# Zaq_HAND_SOLDERING.net
KiCad netlist of a schematic drawn in EAGLE
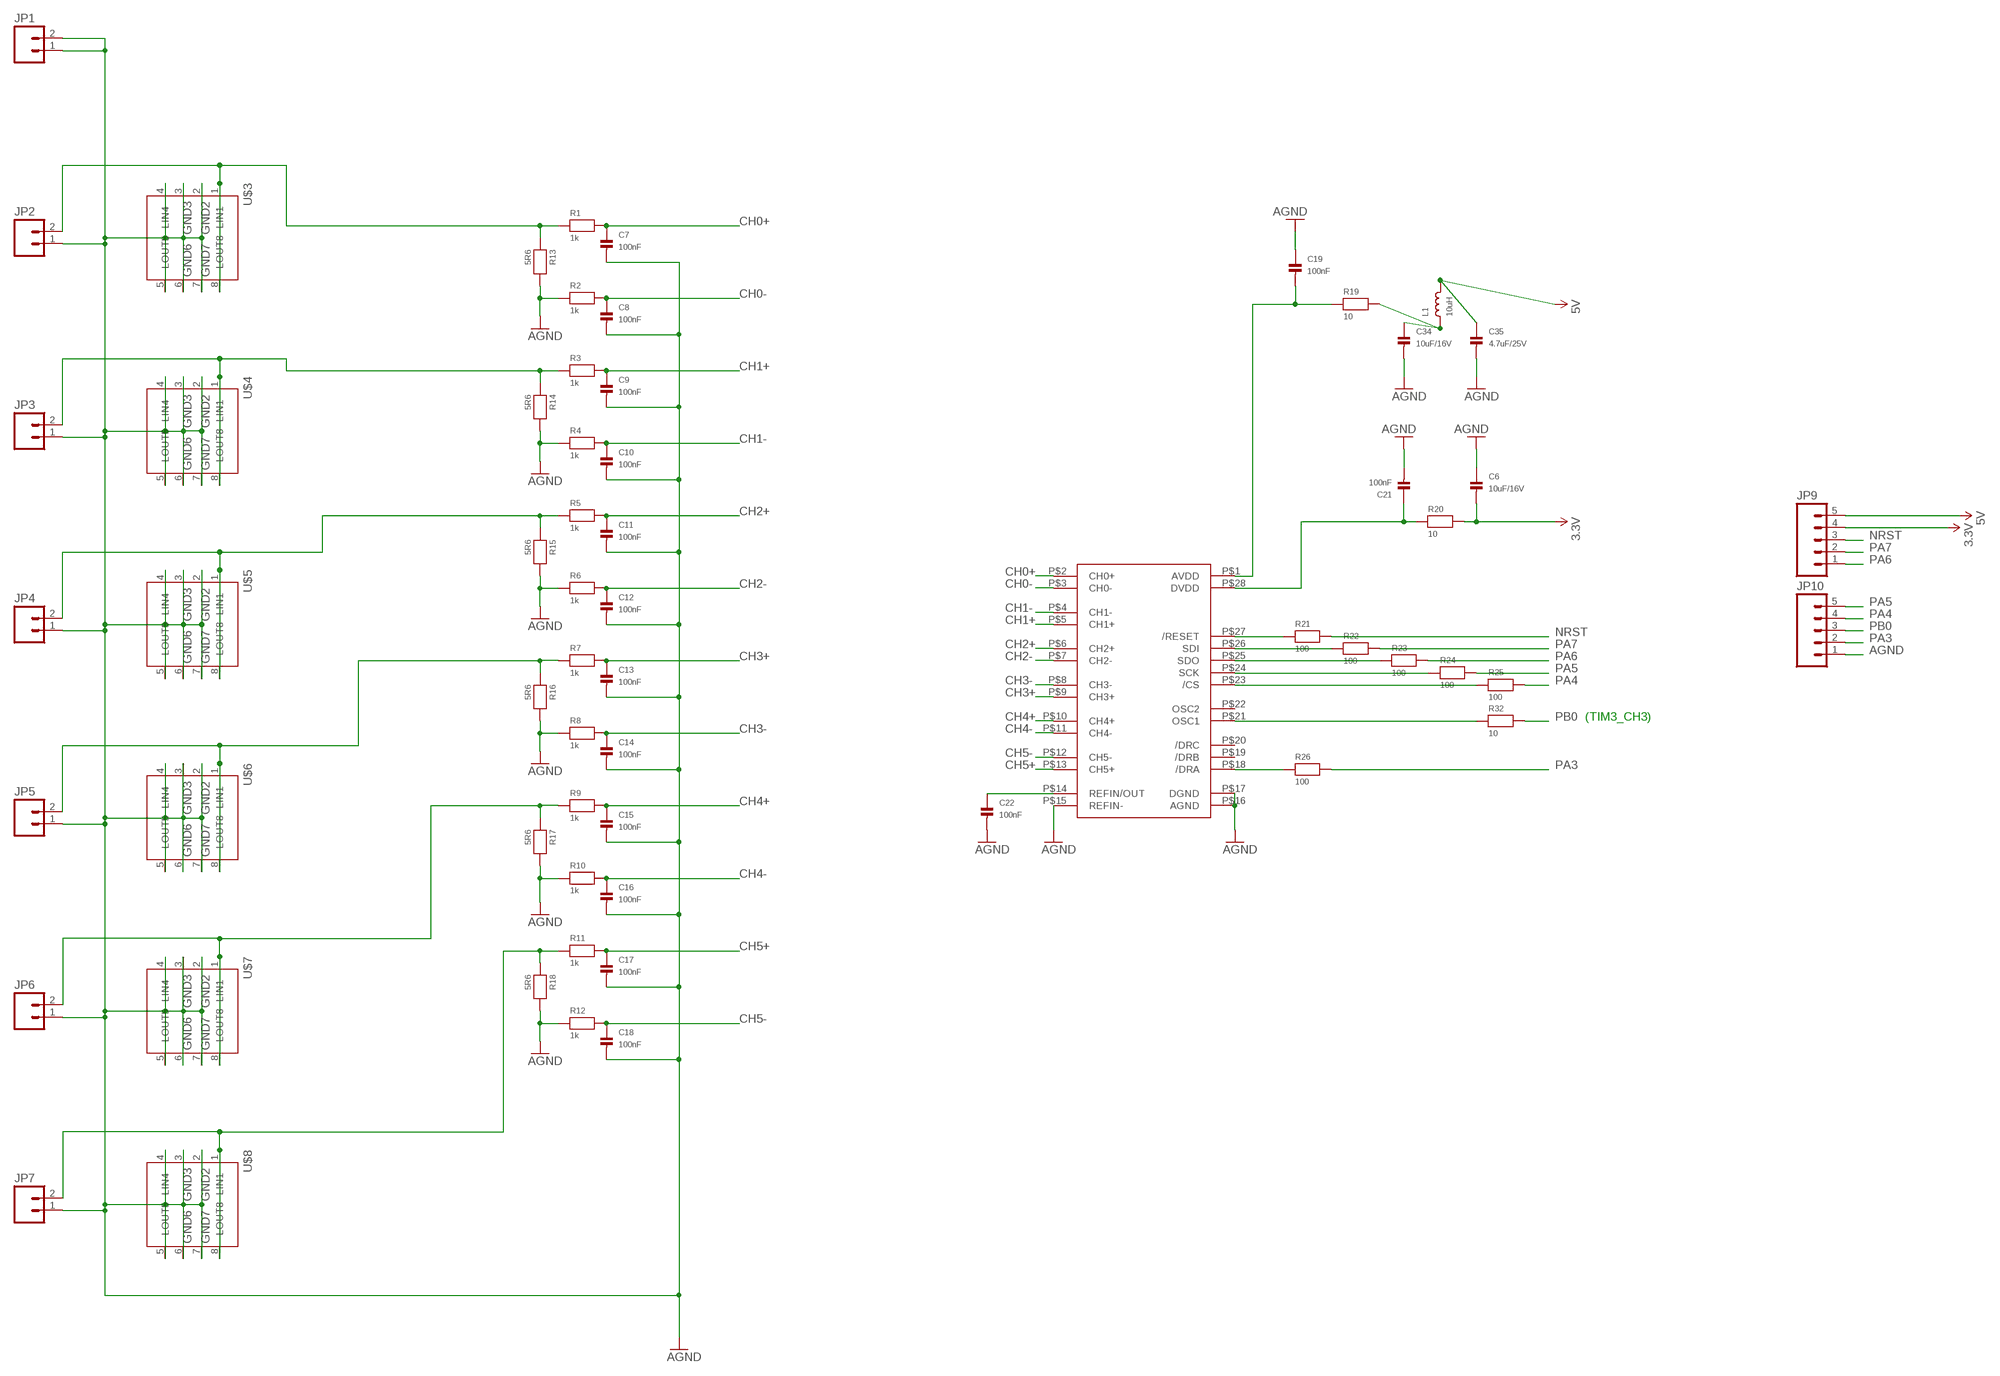
[diagram p0: schematic, sheet 1]

(export (version "E")
  (design (tool "Eeschema 10.0.6"))
  (components
    (comp (ref ".")
      (value "MCP3903")
      (footprint "eagle-import:SSOP-28")
      (libsource (lib "eagle-import") (part "MCP3903"))
    )
    (comp (ref "C6")
      (value "10uF/16V")
      (footprint "eagle-import:_0805MP")
      (libsource (lib "eagle-import") (part "CAP_CERAMIC_0805MP"))
    )
    (comp (ref "C7")
      (value "100nF")
      (footprint "eagle-import:_0805MP")
      (libsource (lib "eagle-import") (part "CAP_CERAMIC_0805MP"))
    )
    (comp (ref "C8")
      (value "100nF")
      (footprint "eagle-import:_0805MP")
      (libsource (lib "eagle-import") (part "CAP_CERAMIC_0805MP"))
    )
    (comp (ref "C9")
      (value "100nF")
      (footprint "eagle-import:_0805MP")
      (libsource (lib "eagle-import") (part "CAP_CERAMIC_0805MP"))
    )
    (comp (ref "C10")
      (value "100nF")
      (footprint "eagle-import:_0805MP")
      (libsource (lib "eagle-import") (part "CAP_CERAMIC_0805MP"))
    )
    (comp (ref "C11")
      (value "100nF")
      (footprint "eagle-import:_0805MP")
      (libsource (lib "eagle-import") (part "CAP_CERAMIC_0805MP"))
    )
    (comp (ref "C12")
      (value "100nF")
      (footprint "eagle-import:_0805MP")
      (libsource (lib "eagle-import") (part "CAP_CERAMIC_0805MP"))
    )
    (comp (ref "C13")
      (value "100nF")
      (footprint "eagle-import:_0805MP")
      (libsource (lib "eagle-import") (part "CAP_CERAMIC_0805MP"))
    )
    (comp (ref "C14")
      (value "100nF")
      (footprint "eagle-import:_0805MP")
      (libsource (lib "eagle-import") (part "CAP_CERAMIC_0805MP"))
    )
    (comp (ref "C15")
      (value "100nF")
      (footprint "eagle-import:_0805MP")
      (libsource (lib "eagle-import") (part "CAP_CERAMIC_0805MP"))
    )
    (comp (ref "C16")
      (value "100nF")
      (footprint "eagle-import:_0805MP")
      (libsource (lib "eagle-import") (part "CAP_CERAMIC_0805MP"))
    )
    (comp (ref "C17")
      (value "100nF")
      (footprint "eagle-import:_0805MP")
      (libsource (lib "eagle-import") (part "CAP_CERAMIC_0805MP"))
    )
    (comp (ref "C18")
      (value "100nF")
      (footprint "eagle-import:_0805MP")
      (libsource (lib "eagle-import") (part "CAP_CERAMIC_0805MP"))
    )
    (comp (ref "C19")
      (value "100nF")
      (footprint "eagle-import:_0805MP")
      (libsource (lib "eagle-import") (part "CAP_CERAMIC_0805MP"))
    )
    (comp (ref "C21")
      (value "100nF")
      (footprint "eagle-import:_0805MP")
      (libsource (lib "eagle-import") (part "CAP_CERAMIC_0805MP"))
    )
    (comp (ref "C22")
      (value "100nF")
      (footprint "eagle-import:_0805MP")
      (libsource (lib "eagle-import") (part "CAP_CERAMIC_0805MP"))
    )
    (comp (ref "C34")
      (value "10uF/16V")
      (footprint "eagle-import:_0805MP")
      (libsource (lib "eagle-import") (part "CAP_CERAMIC_0805MP"))
    )
    (comp (ref "C35")
      (value "4.7uF/25V")
      (footprint "eagle-import:_0805MP")
      (libsource (lib "eagle-import") (part "CAP_CERAMIC_0805MP"))
    )
    (comp (ref "JP1")
      (value "M025MM")
      (footprint "eagle-import:SCREWTERMINAL-5MM-2")
      (libsource (lib "eagle-import") (part "M025MM"))
    )
    (comp (ref "JP2")
      (value "M025MM")
      (footprint "eagle-import:SCREWTERMINAL-5MM-2")
      (libsource (lib "eagle-import") (part "M025MM"))
    )
    (comp (ref "JP3")
      (value "M025MM")
      (footprint "eagle-import:SCREWTERMINAL-5MM-2")
      (libsource (lib "eagle-import") (part "M025MM"))
    )
    (comp (ref "JP4")
      (value "M025MM")
      (footprint "eagle-import:SCREWTERMINAL-5MM-2")
      (libsource (lib "eagle-import") (part "M025MM"))
    )
    (comp (ref "JP5")
      (value "M025MM")
      (footprint "eagle-import:SCREWTERMINAL-5MM-2")
      (libsource (lib "eagle-import") (part "M025MM"))
    )
    (comp (ref "JP6")
      (value "M025MM")
      (footprint "eagle-import:SCREWTERMINAL-5MM-2")
      (libsource (lib "eagle-import") (part "M025MM"))
    )
    (comp (ref "JP7")
      (value "M025MM")
      (footprint "eagle-import:SCREWTERMINAL-5MM-2")
      (libsource (lib "eagle-import") (part "M025MM"))
    )
    (comp (ref "JP9")
      (value "M05PTH_LONGPADS")
      (footprint "eagle-import:1X05_LONGPADS")
      (libsource (lib "eagle-import") (part "M05PTH_LONGPADS"))
    )
    (comp (ref "JP10")
      (value "M05PTH_LONGPADS")
      (footprint "eagle-import:1X05_LONGPADS")
      (libsource (lib "eagle-import") (part "M05PTH_LONGPADS"))
    )
    (comp (ref "L1")
      (value "10uH")
      (footprint "eagle-import:_0805MP")
      (libsource (lib "eagle-import") (part "INDUCTOR_0805MP"))
    )
    (comp (ref "R1")
      (value "1k")
      (footprint "eagle-import:_0805MP")
      (libsource (lib "eagle-import") (part "RESISTOR_0805MP"))
    )
    (comp (ref "R2")
      (value "1k")
      (footprint "eagle-import:_0805MP")
      (libsource (lib "eagle-import") (part "RESISTOR_0805MP"))
    )
    (comp (ref "R3")
      (value "1k")
      (footprint "eagle-import:_0805MP")
      (libsource (lib "eagle-import") (part "RESISTOR_0805MP"))
    )
    (comp (ref "R4")
      (value "1k")
      (footprint "eagle-import:_0805MP")
      (libsource (lib "eagle-import") (part "RESISTOR_0805MP"))
    )
    (comp (ref "R5")
      (value "1k")
      (footprint "eagle-import:_0805MP")
      (libsource (lib "eagle-import") (part "RESISTOR_0805MP"))
    )
    (comp (ref "R6")
      (value "1k")
      (footprint "eagle-import:_0805MP")
      (libsource (lib "eagle-import") (part "RESISTOR_0805MP"))
    )
    (comp (ref "R7")
      (value "1k")
      (footprint "eagle-import:_0805MP")
      (libsource (lib "eagle-import") (part "RESISTOR_0805MP"))
    )
    (comp (ref "R8")
      (value "1k")
      (footprint "eagle-import:_0805MP")
      (libsource (lib "eagle-import") (part "RESISTOR_0805MP"))
    )
    (comp (ref "R9")
      (value "1k")
      (footprint "eagle-import:_0805MP")
      (libsource (lib "eagle-import") (part "RESISTOR_0805MP"))
    )
    (comp (ref "R10")
      (value "1k")
      (footprint "eagle-import:_0805MP")
      (libsource (lib "eagle-import") (part "RESISTOR_0805MP"))
    )
    (comp (ref "R11")
      (value "1k")
      (footprint "eagle-import:_0805MP")
      (libsource (lib "eagle-import") (part "RESISTOR_0805MP"))
    )
    (comp (ref "R12")
      (value "1k")
      (footprint "eagle-import:_0805MP")
      (libsource (lib "eagle-import") (part "RESISTOR_0805MP"))
    )
    (comp (ref "R13")
      (value "5R6")
      (footprint "eagle-import:1206")
      (libsource (lib "eagle-import") (part "RESISTOR1206"))
    )
    (comp (ref "R14")
      (value "5R6")
      (footprint "eagle-import:1206")
      (libsource (lib "eagle-import") (part "RESISTOR1206"))
    )
    (comp (ref "R15")
      (value "5R6")
      (footprint "eagle-import:1206")
      (libsource (lib "eagle-import") (part "RESISTOR1206"))
    )
    (comp (ref "R16")
      (value "5R6")
      (footprint "eagle-import:1206")
      (libsource (lib "eagle-import") (part "RESISTOR1206"))
    )
    (comp (ref "R17")
      (value "5R6")
      (footprint "eagle-import:1206")
      (libsource (lib "eagle-import") (part "RESISTOR1206"))
    )
    (comp (ref "R18")
      (value "5R6")
      (footprint "eagle-import:1206")
      (libsource (lib "eagle-import") (part "RESISTOR1206"))
    )
    (comp (ref "R19")
      (value "10")
      (footprint "eagle-import:_0805MP")
      (libsource (lib "eagle-import") (part "RESISTOR_0805MP"))
    )
    (comp (ref "R20")
      (value "10")
      (footprint "eagle-import:_0805MP")
      (libsource (lib "eagle-import") (part "RESISTOR_0805MP"))
    )
    (comp (ref "R21")
      (value "100")
      (footprint "eagle-import:_0805MP")
      (libsource (lib "eagle-import") (part "RESISTOR_0805MP"))
    )
    (comp (ref "R22")
      (value "100")
      (footprint "eagle-import:_0805MP")
      (libsource (lib "eagle-import") (part "RESISTOR_0805MP"))
    )
    (comp (ref "R23")
      (value "100")
      (footprint "eagle-import:_0805MP")
      (libsource (lib "eagle-import") (part "RESISTOR_0805MP"))
    )
    (comp (ref "R24")
      (value "100")
      (footprint "eagle-import:_0805MP")
      (libsource (lib "eagle-import") (part "RESISTOR_0805MP"))
    )
    (comp (ref "R25")
      (value "100")
      (footprint "eagle-import:_0805MP")
      (libsource (lib "eagle-import") (part "RESISTOR_0805MP"))
    )
    (comp (ref "R26")
      (value "100")
      (footprint "eagle-import:_0805MP")
      (libsource (lib "eagle-import") (part "RESISTOR_0805MP"))
    )
    (comp (ref "R32")
      (value "10")
      (footprint "eagle-import:_0805MP")
      (libsource (lib "eagle-import") (part "RESISTOR_0805MP"))
    )
    (comp (ref "U$3")
      (value "LC03_3V3")
      (footprint "eagle-import:SO8")
      (libsource (lib "eagle-import") (part "LC03_3V3"))
    )
    (comp (ref "U$4")
      (value "LC03_3V3")
      (footprint "eagle-import:SO8")
      (libsource (lib "eagle-import") (part "LC03_3V3"))
    )
    (comp (ref "U$5")
      (value "LC03_3V3")
      (footprint "eagle-import:SO8")
      (libsource (lib "eagle-import") (part "LC03_3V3"))
    )
    (comp (ref "U$6")
      (value "LC03_3V3")
      (footprint "eagle-import:SO8")
      (libsource (lib "eagle-import") (part "LC03_3V3"))
    )
    (comp (ref "U$7")
      (value "LC03_3V3")
      (footprint "eagle-import:SO8")
      (libsource (lib "eagle-import") (part "LC03_3V3"))
    )
    (comp (ref "U$8")
      (value "LC03_3V3")
      (footprint "eagle-import:SO8")
      (libsource (lib "eagle-import") (part "LC03_3V3"))
    )
  )
  (nets
    (net (code "1") (name "/CH0+") (class "Default")
      (node (ref ".") (pin "P$2") (pinfunction "CH0+_P$2") (pintype "bidirectional"))
      (node (ref "C7") (pin "1") (pinfunction "P$1_1") (pintype "passive"))
      (node (ref "R1") (pin "2") (pinfunction "2_2") (pintype "passive"))
    )
    (net (code "2") (name "/CH0-") (class "Default")
      (node (ref ".") (pin "P$3") (pinfunction "CH0-_P$3") (pintype "bidirectional"))
      (node (ref "C8") (pin "1") (pinfunction "P$1_1") (pintype "passive"))
      (node (ref "R2") (pin "2") (pinfunction "2_2") (pintype "passive"))
    )
    (net (code "3") (name "/CH1+") (class "Default")
      (node (ref ".") (pin "P$5") (pinfunction "CH1+_P$5") (pintype "bidirectional"))
      (node (ref "C9") (pin "1") (pinfunction "P$1_1") (pintype "passive"))
      (node (ref "R3") (pin "2") (pinfunction "2_2") (pintype "passive"))
    )
    (net (code "4") (name "/CH1-") (class "Default")
      (node (ref ".") (pin "P$4") (pinfunction "CH1-_P$4") (pintype "bidirectional"))
      (node (ref "C10") (pin "1") (pinfunction "P$1_1") (pintype "passive"))
      (node (ref "R4") (pin "2") (pinfunction "2_2") (pintype "passive"))
    )
    (net (code "5") (name "/CH2+") (class "Default")
      (node (ref ".") (pin "P$6") (pinfunction "CH2+_P$6") (pintype "bidirectional"))
      (node (ref "C11") (pin "1") (pinfunction "P$1_1") (pintype "passive"))
      (node (ref "R5") (pin "2") (pinfunction "2_2") (pintype "passive"))
    )
    (net (code "6") (name "/CH2-") (class "Default")
      (node (ref ".") (pin "P$7") (pinfunction "CH2-_P$7") (pintype "bidirectional"))
      (node (ref "C12") (pin "1") (pinfunction "P$1_1") (pintype "passive"))
      (node (ref "R6") (pin "2") (pinfunction "2_2") (pintype "passive"))
    )
    (net (code "7") (name "/CH3+") (class "Default")
      (node (ref ".") (pin "P$9") (pinfunction "CH3+_P$9") (pintype "bidirectional"))
      (node (ref "C13") (pin "1") (pinfunction "P$1_1") (pintype "passive"))
      (node (ref "R7") (pin "2") (pinfunction "2_2") (pintype "passive"))
    )
    (net (code "8") (name "/CH3-") (class "Default")
      (node (ref ".") (pin "P$8") (pinfunction "CH3-_P$8") (pintype "bidirectional"))
      (node (ref "C14") (pin "1") (pinfunction "P$1_1") (pintype "passive"))
      (node (ref "R8") (pin "2") (pinfunction "2_2") (pintype "passive"))
    )
    (net (code "9") (name "/CH4+") (class "Default")
      (node (ref ".") (pin "P$10") (pinfunction "CH4+_P$10") (pintype "bidirectional"))
      (node (ref "C15") (pin "1") (pinfunction "P$1_1") (pintype "passive"))
      (node (ref "R9") (pin "2") (pinfunction "2_2") (pintype "passive"))
    )
    (net (code "10") (name "/CH4-") (class "Default")
      (node (ref ".") (pin "P$11") (pinfunction "CH4-_P$11") (pintype "bidirectional"))
      (node (ref "C16") (pin "1") (pinfunction "P$1_1") (pintype "passive"))
      (node (ref "R10") (pin "2") (pinfunction "2_2") (pintype "passive"))
    )
    (net (code "11") (name "/CH5+") (class "Default")
      (node (ref ".") (pin "P$13") (pinfunction "CH5+_P$13") (pintype "bidirectional"))
      (node (ref "C17") (pin "1") (pinfunction "P$1_1") (pintype "passive"))
      (node (ref "R11") (pin "2") (pinfunction "2_2") (pintype "passive"))
    )
    (net (code "12") (name "/CH5-") (class "Default")
      (node (ref ".") (pin "P$12") (pinfunction "CH5-_P$12") (pintype "bidirectional"))
      (node (ref "C18") (pin "1") (pinfunction "P$1_1") (pintype "passive"))
      (node (ref "R12") (pin "2") (pinfunction "2_2") (pintype "passive"))
    )
    (net (code "13") (name "/NRST") (class "Default")
      (node (ref "JP9") (pin "3") (pinfunction "3_3") (pintype "passive"))
      (node (ref "R21") (pin "2") (pinfunction "2_2") (pintype "passive"))
    )
    (net (code "14") (name "/PA3") (class "Default")
      (node (ref "JP10") (pin "2") (pinfunction "2_2") (pintype "passive"))
      (node (ref "R26") (pin "2") (pinfunction "2_2") (pintype "passive"))
    )
    (net (code "15") (name "/PA4") (class "Default")
      (node (ref "JP10") (pin "4") (pinfunction "4_4") (pintype "passive"))
      (node (ref "R25") (pin "2") (pinfunction "2_2") (pintype "passive"))
    )
    (net (code "16") (name "/PA5") (class "Default")
      (node (ref "JP10") (pin "5") (pinfunction "5_5") (pintype "passive"))
      (node (ref "R24") (pin "2") (pinfunction "2_2") (pintype "passive"))
    )
    (net (code "17") (name "/PA6") (class "Default")
      (node (ref "JP9") (pin "1") (pinfunction "1_1") (pintype "passive"))
      (node (ref "R23") (pin "2") (pinfunction "2_2") (pintype "passive"))
    )
    (net (code "18") (name "/PA7") (class "Default")
      (node (ref "JP9") (pin "2") (pinfunction "2_2") (pintype "passive"))
      (node (ref "R22") (pin "2") (pinfunction "2_2") (pintype "passive"))
    )
    (net (code "19") (name "/PB0") (class "Default")
      (node (ref "JP10") (pin "3") (pinfunction "3_3") (pintype "passive"))
      (node (ref "R32") (pin "2") (pinfunction "2_2") (pintype "passive"))
    )
    (net (code "20") (name "3.3V") (class "Default")
      (node (ref "C6") (pin "2") (pinfunction "P$2_2") (pintype "passive"))
      (node (ref "JP9") (pin "4") (pinfunction "4_4") (pintype "passive"))
      (node (ref "R20") (pin "2") (pinfunction "2_2") (pintype "passive"))
    )
    (net (code "21") (name "5V") (class "Default")
      (node (ref "C35") (pin "1") (pinfunction "P$1_1") (pintype "passive"))
      (node (ref "JP9") (pin "5") (pinfunction "5_5") (pintype "passive"))
      (node (ref "L1") (pin "2") (pinfunction "2_2") (pintype "passive"))
    )
    (net (code "22") (name "AGND") (class "Default")
      (node (ref ".") (pin "P$15") (pinfunction "REFIN-_P$15") (pintype "bidirectional"))
      (node (ref ".") (pin "P$16") (pinfunction "AGND_P$16") (pintype "bidirectional"))
      (node (ref ".") (pin "P$17") (pinfunction "DGND_P$17") (pintype "bidirectional"))
      (node (ref "C10") (pin "2") (pinfunction "P$2_2") (pintype "passive"))
      (node (ref "C11") (pin "2") (pinfunction "P$2_2") (pintype "passive"))
      (node (ref "C12") (pin "2") (pinfunction "P$2_2") (pintype "passive"))
      (node (ref "C13") (pin "2") (pinfunction "P$2_2") (pintype "passive"))
      (node (ref "C14") (pin "2") (pinfunction "P$2_2") (pintype "passive"))
      (node (ref "C15") (pin "2") (pinfunction "P$2_2") (pintype "passive"))
      (node (ref "C16") (pin "2") (pinfunction "P$2_2") (pintype "passive"))
      (node (ref "C17") (pin "2") (pinfunction "P$2_2") (pintype "passive"))
      (node (ref "C18") (pin "2") (pinfunction "P$2_2") (pintype "passive"))
      (node (ref "C19") (pin "1") (pinfunction "P$1_1") (pintype "passive"))
      (node (ref "C21") (pin "2") (pinfunction "P$2_2") (pintype "passive"))
      (node (ref "C22") (pin "2") (pinfunction "P$2_2") (pintype "passive"))
      (node (ref "C34") (pin "2") (pinfunction "P$2_2") (pintype "passive"))
      (node (ref "C35") (pin "2") (pinfunction "P$2_2") (pintype "passive"))
      (node (ref "C6") (pin "1") (pinfunction "P$1_1") (pintype "passive"))
      (node (ref "C7") (pin "2") (pinfunction "P$2_2") (pintype "passive"))
      (node (ref "C8") (pin "2") (pinfunction "P$2_2") (pintype "passive"))
      (node (ref "C9") (pin "2") (pinfunction "P$2_2") (pintype "passive"))
      (node (ref "JP1") (pin "1") (pinfunction "1_1") (pintype "passive"))
      (node (ref "JP1") (pin "2") (pinfunction "2_2") (pintype "passive"))
      (node (ref "JP10") (pin "1") (pinfunction "1_1") (pintype "passive"))
      (node (ref "JP2") (pin "1") (pinfunction "1_1") (pintype "passive"))
      (node (ref "JP3") (pin "1") (pinfunction "1_1") (pintype "passive"))
      (node (ref "JP4") (pin "1") (pinfunction "1_1") (pintype "passive"))
      (node (ref "JP5") (pin "1") (pinfunction "1_1") (pintype "passive"))
      (node (ref "JP6") (pin "1") (pinfunction "1_1") (pintype "passive"))
      (node (ref "JP7") (pin "1") (pinfunction "1_1") (pintype "passive"))
      (node (ref "R10") (pin "1") (pinfunction "1_1") (pintype "passive"))
      (node (ref "R12") (pin "1") (pinfunction "1_1") (pintype "passive"))
      (node (ref "R13") (pin "2") (pinfunction "2_2") (pintype "passive"))
      (node (ref "R14") (pin "2") (pinfunction "2_2") (pintype "passive"))
      (node (ref "R15") (pin "2") (pinfunction "2_2") (pintype "passive"))
      (node (ref "R16") (pin "2") (pinfunction "2_2") (pintype "passive"))
      (node (ref "R17") (pin "2") (pinfunction "2_2") (pintype "passive"))
      (node (ref "R18") (pin "2") (pinfunction "2_2") (pintype "passive"))
      (node (ref "R2") (pin "1") (pinfunction "1_1") (pintype "passive"))
      (node (ref "R4") (pin "1") (pinfunction "1_1") (pintype "passive"))
      (node (ref "R6") (pin "1") (pinfunction "1_1") (pintype "passive"))
      (node (ref "R8") (pin "1") (pinfunction "1_1") (pintype "passive"))
      (node (ref "U$3") (pin "2") (pinfunction "GND_2_2") (pintype "power_in"))
      (node (ref "U$3") (pin "3") (pinfunction "GND_3_3") (pintype "power_in"))
      (node (ref "U$3") (pin "4") (pinfunction "LIN4_4") (pintype "input"))
      (node (ref "U$3") (pin "5") (pinfunction "LOUT5_5") (pintype "input"))
      (node (ref "U$3") (pin "6") (pinfunction "GND_6_6") (pintype "power_in"))
      (node (ref "U$3") (pin "7") (pinfunction "GND_7_7") (pintype "power_in"))
      (node (ref "U$4") (pin "2") (pinfunction "GND_2_2") (pintype "power_in"))
      (node (ref "U$4") (pin "3") (pinfunction "GND_3_3") (pintype "power_in"))
      (node (ref "U$4") (pin "4") (pinfunction "LIN4_4") (pintype "input"))
      (node (ref "U$4") (pin "5") (pinfunction "LOUT5_5") (pintype "input"))
      (node (ref "U$4") (pin "6") (pinfunction "GND_6_6") (pintype "power_in"))
      (node (ref "U$4") (pin "7") (pinfunction "GND_7_7") (pintype "power_in"))
      (node (ref "U$5") (pin "2") (pinfunction "GND_2_2") (pintype "power_in"))
      (node (ref "U$5") (pin "3") (pinfunction "GND_3_3") (pintype "power_in"))
      (node (ref "U$5") (pin "4") (pinfunction "LIN4_4") (pintype "input"))
      (node (ref "U$5") (pin "5") (pinfunction "LOUT5_5") (pintype "input"))
      (node (ref "U$5") (pin "6") (pinfunction "GND_6_6") (pintype "power_in"))
      (node (ref "U$5") (pin "7") (pinfunction "GND_7_7") (pintype "power_in"))
      (node (ref "U$6") (pin "2") (pinfunction "GND_2_2") (pintype "power_in"))
      (node (ref "U$6") (pin "3") (pinfunction "GND_3_3") (pintype "power_in"))
      (node (ref "U$6") (pin "4") (pinfunction "LIN4_4") (pintype "input"))
      (node (ref "U$6") (pin "5") (pinfunction "LOUT5_5") (pintype "input"))
      (node (ref "U$6") (pin "6") (pinfunction "GND_6_6") (pintype "power_in"))
      (node (ref "U$6") (pin "7") (pinfunction "GND_7_7") (pintype "power_in"))
      (node (ref "U$7") (pin "2") (pinfunction "GND_2_2") (pintype "power_in"))
      (node (ref "U$7") (pin "3") (pinfunction "GND_3_3") (pintype "power_in"))
      (node (ref "U$7") (pin "4") (pinfunction "LIN4_4") (pintype "input"))
      (node (ref "U$7") (pin "5") (pinfunction "LOUT5_5") (pintype "input"))
      (node (ref "U$7") (pin "6") (pinfunction "GND_6_6") (pintype "power_in"))
      (node (ref "U$7") (pin "7") (pinfunction "GND_7_7") (pintype "power_in"))
      (node (ref "U$8") (pin "2") (pinfunction "GND_2_2") (pintype "power_in"))
      (node (ref "U$8") (pin "3") (pinfunction "GND_3_3") (pintype "power_in"))
      (node (ref "U$8") (pin "4") (pinfunction "LIN4_4") (pintype "input"))
      (node (ref "U$8") (pin "5") (pinfunction "LOUT5_5") (pintype "input"))
      (node (ref "U$8") (pin "6") (pinfunction "GND_6_6") (pintype "power_in"))
      (node (ref "U$8") (pin "7") (pinfunction "GND_7_7") (pintype "power_in"))
    )
    (net (code "23") (name "Net-(.-AVDD)") (class "Default")
      (node (ref ".") (pin "P$1") (pinfunction "AVDD_P$1") (pintype "bidirectional"))
      (node (ref "C19") (pin "2") (pinfunction "P$2_2") (pintype "passive"))
      (node (ref "R19") (pin "1") (pinfunction "1_1") (pintype "passive"))
    )
    (net (code "24") (name "Net-(.-DVDD)") (class "Default")
      (node (ref ".") (pin "P$28") (pinfunction "DVDD_P$28") (pintype "bidirectional"))
      (node (ref "C21") (pin "1") (pinfunction "P$1_1") (pintype "passive"))
      (node (ref "R20") (pin "1") (pinfunction "1_1") (pintype "passive"))
    )
    (net (code "25") (name "Net-(.-OSC1)") (class "Default")
      (node (ref ".") (pin "P$21") (pinfunction "OSC1_P$21") (pintype "bidirectional"))
      (node (ref "R32") (pin "1") (pinfunction "1_1") (pintype "passive"))
    )
    (net (code "26") (name "Net-(.-REFIN{slash}OUT)") (class "Default")
      (node (ref ".") (pin "P$14") (pinfunction "REFIN/OUT_P$14") (pintype "bidirectional"))
      (node (ref "C22") (pin "1") (pinfunction "P$1_1") (pintype "passive"))
    )
    (net (code "27") (name "Net-(.-SCK)") (class "Default")
      (node (ref ".") (pin "P$24") (pinfunction "SCK_P$24") (pintype "bidirectional"))
      (node (ref "R24") (pin "1") (pinfunction "1_1") (pintype "passive"))
    )
    (net (code "28") (name "Net-(.-SDI)") (class "Default")
      (node (ref ".") (pin "P$26") (pinfunction "SDI_P$26") (pintype "bidirectional"))
      (node (ref "R22") (pin "1") (pinfunction "1_1") (pintype "passive"))
    )
    (net (code "29") (name "Net-(.-SDO)") (class "Default")
      (node (ref ".") (pin "P$25") (pinfunction "SDO_P$25") (pintype "bidirectional"))
      (node (ref "R23") (pin "1") (pinfunction "1_1") (pintype "passive"))
    )
    (net (code "30") (name "Net-(.-{slash}CS)") (class "Default")
      (node (ref ".") (pin "P$23") (pinfunction "/CS_P$23") (pintype "bidirectional"))
      (node (ref "R25") (pin "1") (pinfunction "1_1") (pintype "passive"))
    )
    (net (code "31") (name "Net-(.-{slash}DRA)") (class "Default")
      (node (ref ".") (pin "P$18") (pinfunction "/DRA_P$18") (pintype "bidirectional"))
      (node (ref "R26") (pin "1") (pinfunction "1_1") (pintype "passive"))
    )
    (net (code "32") (name "Net-(.-{slash}RESET)") (class "Default")
      (node (ref ".") (pin "P$27") (pinfunction "/RESET_P$27") (pintype "bidirectional"))
      (node (ref "R21") (pin "1") (pinfunction "1_1") (pintype "passive"))
    )
    (net (code "33") (name "Net-(C34-P$1)") (class "Default")
      (node (ref "C34") (pin "1") (pinfunction "P$1_1") (pintype "passive"))
      (node (ref "L1") (pin "1") (pinfunction "1_1") (pintype "passive"))
      (node (ref "R19") (pin "2") (pinfunction "2_2") (pintype "passive"))
    )
    (net (code "34") (name "Net-(U$3-LIN1)") (class "Default")
      (node (ref "JP2") (pin "2") (pinfunction "2_2") (pintype "passive"))
      (node (ref "R1") (pin "1") (pinfunction "1_1") (pintype "passive"))
      (node (ref "R13") (pin "1") (pinfunction "1_1") (pintype "passive"))
      (node (ref "U$3") (pin "1") (pinfunction "LIN1_1") (pintype "input"))
      (node (ref "U$3") (pin "8") (pinfunction "LOUT8_8") (pintype "bidirectional"))
    )
    (net (code "35") (name "Net-(U$4-LIN1)") (class "Default")
      (node (ref "JP3") (pin "2") (pinfunction "2_2") (pintype "passive"))
      (node (ref "R14") (pin "1") (pinfunction "1_1") (pintype "passive"))
      (node (ref "R3") (pin "1") (pinfunction "1_1") (pintype "passive"))
      (node (ref "U$4") (pin "1") (pinfunction "LIN1_1") (pintype "input"))
      (node (ref "U$4") (pin "8") (pinfunction "LOUT8_8") (pintype "bidirectional"))
    )
    (net (code "36") (name "Net-(U$5-LIN1)") (class "Default")
      (node (ref "JP4") (pin "2") (pinfunction "2_2") (pintype "passive"))
      (node (ref "R15") (pin "1") (pinfunction "1_1") (pintype "passive"))
      (node (ref "R5") (pin "1") (pinfunction "1_1") (pintype "passive"))
      (node (ref "U$5") (pin "1") (pinfunction "LIN1_1") (pintype "input"))
      (node (ref "U$5") (pin "8") (pinfunction "LOUT8_8") (pintype "bidirectional"))
    )
    (net (code "37") (name "Net-(U$6-LIN1)") (class "Default")
      (node (ref "JP5") (pin "2") (pinfunction "2_2") (pintype "passive"))
      (node (ref "R16") (pin "1") (pinfunction "1_1") (pintype "passive"))
      (node (ref "R7") (pin "1") (pinfunction "1_1") (pintype "passive"))
      (node (ref "U$6") (pin "1") (pinfunction "LIN1_1") (pintype "input"))
      (node (ref "U$6") (pin "8") (pinfunction "LOUT8_8") (pintype "bidirectional"))
    )
    (net (code "38") (name "Net-(U$7-LIN1)") (class "Default")
      (node (ref "JP6") (pin "2") (pinfunction "2_2") (pintype "passive"))
      (node (ref "R17") (pin "1") (pinfunction "1_1") (pintype "passive"))
      (node (ref "R9") (pin "1") (pinfunction "1_1") (pintype "passive"))
      (node (ref "U$7") (pin "1") (pinfunction "LIN1_1") (pintype "input"))
      (node (ref "U$7") (pin "8") (pinfunction "LOUT8_8") (pintype "bidirectional"))
    )
    (net (code "39") (name "Net-(U$8-LIN1)") (class "Default")
      (node (ref "JP7") (pin "2") (pinfunction "2_2") (pintype "passive"))
      (node (ref "R11") (pin "1") (pinfunction "1_1") (pintype "passive"))
      (node (ref "R18") (pin "1") (pinfunction "1_1") (pintype "passive"))
      (node (ref "U$8") (pin "1") (pinfunction "LIN1_1") (pintype "input"))
      (node (ref "U$8") (pin "8") (pinfunction "LOUT8_8") (pintype "bidirectional"))
    )
    (net (code "40") (name "unconnected-(.-OSC2-PadP$22)") (class "Default")
      (node (ref ".") (pin "P$22") (pinfunction "OSC2_P$22") (pintype "bidirectional"))
    )
    (net (code "41") (name "unconnected-(.-{slash}DRB-PadP$19)") (class "Default")
      (node (ref ".") (pin "P$19") (pinfunction "/DRB_P$19") (pintype "bidirectional"))
    )
    (net (code "42") (name "unconnected-(.-{slash}DRC-PadP$20)") (class "Default")
      (node (ref ".") (pin "P$20") (pinfunction "/DRC_P$20") (pintype "bidirectional"))
    )
  )
)
